# power.net
KiCad netlist of a schematic drawn in EAGLE
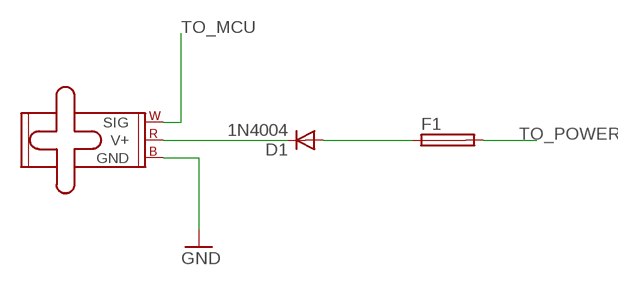
[diagram p0: schematic, sheet 1]

(export (version "E")
  (design (tool "Eeschema 10.0.6"))
  (components
    (comp (ref "D1")
      (value "1N4004")
      (footprint "eagle-import:DO41-10")
      (libsource (lib "eagle-import") (part "1N4004"))
    )
    (comp (ref "F1")
      (value "TE5")
      (footprint "eagle-import:TE5")
      (libsource (lib "eagle-import") (part "TE5"))
    )
    (comp (ref "M1")
      (value "SMALL_SERVO")
      (footprint "eagle-import:1X03")
      (libsource (lib "eagle-import") (part "SMALL_SERVO"))
    )
  )
  (nets
    (net (code "1") (name "/TO_MCU") (class "Default")
      (node (ref "M1") (pin "1") (pinfunction "SIG_1") (pintype "bidirectional"))
    )
    (net (code "2") (name "/TO_POWER") (class "Default")
      (node (ref "F1") (pin "2") (pinfunction "2_2") (pintype "passive"))
    )
    (net (code "3") (name "GND") (class "Default")
      (node (ref "M1") (pin "3") (pinfunction "GND_3") (pintype "bidirectional"))
    )
    (net (code "4") (name "Net-(D1-PadA)") (class "Default")
      (node (ref "D1") (pin "A") (pinfunction "A_A") (pintype "passive"))
      (node (ref "F1") (pin "1") (pinfunction "1_1") (pintype "passive"))
    )
    (net (code "5") (name "Net-(M1-V+)") (class "Default")
      (node (ref "D1") (pin "C") (pinfunction "C_C") (pintype "passive"))
      (node (ref "M1") (pin "2") (pinfunction "V+_2") (pintype "bidirectional"))
    )
  )
)
